# ifamp-rx.net
KiCad netlist of a schematic drawn in Altium Designer
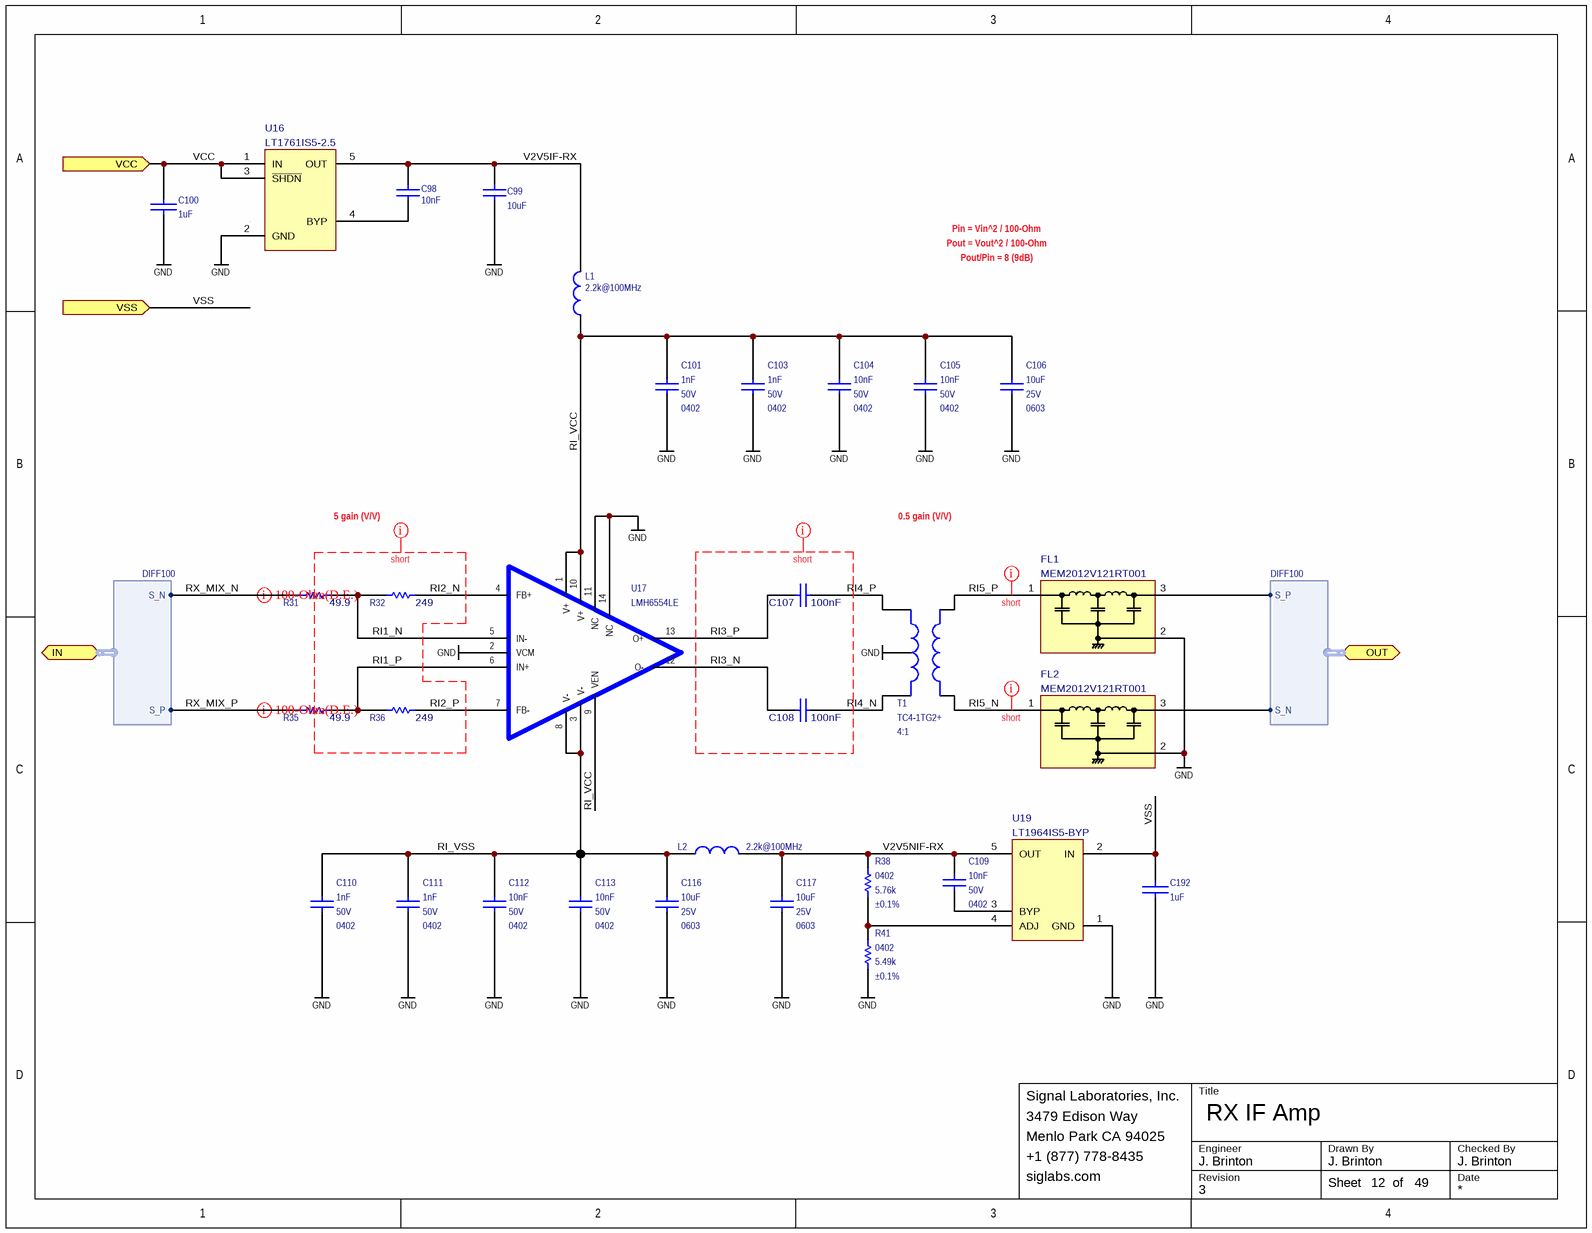
[diagram p0: ifamp-rx.SchDoc]

(export (version "E")
  (design (tool "Eeschema 10.0.6"))
  (components
    (comp (ref "C98")
      (value "10nF")
      (footprint "CAPC100X50X55L25N")
      (description "Ceramic Capacitor 10nF ±10% 50V X7R 0402")
      (fields (field (name "VOLTAGE") "50V") (field (name "MANUFACTURER") "Murata"))
      (libsource (lib "Graviton") (part "CAP 0402"))
    )
    (comp (ref "C99")
      (value "10uF")
      (footprint "CAPC160X80X90L20N")
      (description "Ceramic Capacitor 10uF ±20% 25V X5R 0603")
      (fields (field (name "MANUFACTURER") "Murata") (field (name "VOLTAGE") "25V"))
      (libsource (lib "generic") (part "CAP 0603"))
    )
    (comp (ref "C100")
      (value "1uF")
      (footprint "CAPC100X50X55L25N")
      (description "Ceramic Capacitor 1uF ±10% 10V X5R 0402")
      (fields (field (name "MANUFACTURER") "Murata") (field (name "TOLERANCE") "±10%"))
      (libsource (lib "*") (part "CAP"))
    )
    (comp (ref "C101")
      (value "1nF")
      (footprint "CAPC100X50X55L25N")
      (description "Ceramic Capacitor 1nF ±5% 50V NP0 0402")
      (fields
        (field (name "VOLTAGE") "50V")
        (field (name "MANUFACTURER") "TDK")
        (field (name "PACKAGE") "0402")
        (field (name "TOLERANCE") "±5%")
      )
      (libsource (lib "Graviton") (part "CAP 0402"))
    )
    (comp (ref "C103")
      (value "1nF")
      (footprint "CAPC100X50X55L25N")
      (description "Ceramic Capacitor 1nF ±5% 50V NP0 0402")
      (fields
        (field (name "VOLTAGE") "50V")
        (field (name "MANUFACTURER") "TDK")
        (field (name "PACKAGE") "0402")
        (field (name "TOLERANCE") "±5%")
      )
      (libsource (lib "Graviton") (part "CAP 0402"))
    )
    (comp (ref "C104")
      (value "10nF")
      (footprint "CAPC100X50X55L25N")
      (description "Ceramic Capacitor 10nF ±10% 50V X7R 0402")
      (fields
        (field (name "VOLTAGE") "50V")
        (field (name "MANUFACTURER") "Murata")
        (field (name "PACKAGE") "0402")
        (field (name "TOLERANCE") "±10%")
      )
      (libsource (lib "Graviton") (part "CAP 0402"))
    )
    (comp (ref "C105")
      (value "10nF")
      (footprint "CAPC100X50X55L25N")
      (description "Ceramic Capacitor 10nF ±10% 50V X7R 0402")
      (fields
        (field (name "VOLTAGE") "50V")
        (field (name "MANUFACTURER") "Murata")
        (field (name "PACKAGE") "0402")
        (field (name "TOLERANCE") "±10%")
      )
      (libsource (lib "Graviton") (part "CAP 0402"))
    )
    (comp (ref "C106")
      (value "10uF")
      (footprint "CAPC160X80X90L20N")
      (description "Ceramic Capacitor 10uF ±20% 25V X5R 0603")
      (fields
        (field (name "MANUFACTURER") "Murata")
        (field (name "VOLTAGE") "25V")
        (field (name "PACKAGE") "0603")
        (field (name "TOLERANCE") "±20%")
      )
      (libsource (lib "generic") (part "CAP 0603"))
    )
    (comp (ref "C107")
      (value "100nF")
      (footprint "CAPC100X50X55L25N")
      (description "Ceramic Capacitor 100nF ±10% 25V X7R 0402")
      (fields (field (name "MANUFACTURER") "Yageo") (field (name "TOLERANCE") "±10%"))
      (libsource (lib "capacitors") (part "CAP"))
    )
    (comp (ref "C108")
      (value "100nF")
      (footprint "CAPC100X50X55L25N")
      (description "Ceramic Capacitor 100nF ±10% 25V X7R 0402")
      (fields (field (name "MANUFACTURER") "Yageo") (field (name "TOLERANCE") "±10%"))
      (libsource (lib "capacitors") (part "CAP"))
    )
    (comp (ref "C109")
      (value "10nF")
      (footprint "CAPC100X50X55L25N")
      (description "Ceramic Capacitor 10nF ±10% 50V X7R 0402")
      (fields
        (field (name "VOLTAGE") "50V")
        (field (name "MANUFACTURER") "Murata")
        (field (name "PACKAGE") "0402")
        (field (name "TOLERANCE") "±10%")
      )
      (libsource (lib "Graviton") (part "CAP 0402"))
    )
    (comp (ref "C110")
      (value "1nF")
      (footprint "CAPC100X50X55L25N")
      (description "Ceramic Capacitor 1nF ±5% 50V NP0 0402")
      (fields
        (field (name "VOLTAGE") "50V")
        (field (name "MANUFACTURER") "TDK")
        (field (name "PACKAGE") "0402")
        (field (name "TOLERANCE") "±5%")
      )
      (libsource (lib "Graviton") (part "CAP 0402"))
    )
    (comp (ref "C111")
      (value "1nF")
      (footprint "CAPC100X50X55L25N")
      (description "Ceramic Capacitor 1nF ±5% 50V NP0 0402")
      (fields
        (field (name "VOLTAGE") "50V")
        (field (name "MANUFACTURER") "TDK")
        (field (name "PACKAGE") "0402")
        (field (name "TOLERANCE") "±5%")
      )
      (libsource (lib "Graviton") (part "CAP 0402"))
    )
    (comp (ref "C112")
      (value "10nF")
      (footprint "CAPC100X50X55L25N")
      (description "Ceramic Capacitor 10nF ±10% 50V X7R 0402")
      (fields
        (field (name "VOLTAGE") "50V")
        (field (name "MANUFACTURER") "Murata")
        (field (name "PACKAGE") "0402")
        (field (name "TOLERANCE") "±10%")
      )
      (libsource (lib "Graviton") (part "CAP 0402"))
    )
    (comp (ref "C113")
      (value "10nF")
      (footprint "CAPC100X50X55L25N")
      (description "Ceramic Capacitor 10nF ±10% 50V X7R 0402")
      (fields
        (field (name "VOLTAGE") "50V")
        (field (name "MANUFACTURER") "Murata")
        (field (name "PACKAGE") "0402")
        (field (name "TOLERANCE") "±10%")
      )
      (libsource (lib "Graviton") (part "CAP 0402"))
    )
    (comp (ref "C116")
      (value "10uF")
      (footprint "CAPC160X80X90L20N")
      (description "Ceramic Capacitor 10uF ±20% 25V X5R 0603")
      (fields
        (field (name "MANUFACTURER") "Murata")
        (field (name "VOLTAGE") "25V")
        (field (name "PACKAGE") "0603")
        (field (name "TOLERANCE") "±20%")
      )
      (libsource (lib "generic") (part "CAP 0603"))
    )
    (comp (ref "C117")
      (value "10uF")
      (footprint "CAPC160X80X90L20N")
      (description "Ceramic Capacitor 10uF ±20% 25V X5R 0603")
      (fields
        (field (name "MANUFACTURER") "Murata")
        (field (name "VOLTAGE") "25V")
        (field (name "PACKAGE") "0603")
        (field (name "TOLERANCE") "±20%")
      )
      (libsource (lib "generic") (part "CAP 0603"))
    )
    (comp (ref "C192")
      (value "1uF")
      (footprint "CAPC100X50X55L25N")
      (description "Ceramic Capacitor 1uF ±10% 10V X5R 0402")
      (fields (field (name "MANUFACTURER") "Murata") (field (name "TOLERANCE") "±10%"))
      (libsource (lib "*") (part "CAP"))
    )
    (comp (ref "FL1")
      (value "MEM2012V121RT001")
      (footprint "tdk:MEM2012V")
      (description "MEM2012 Series 120 MHz 10V 100mA SMT Signal Line 3-Terminal Filter")
      (fields (field (name "MANUFACTURER") "TDK"))
      (libsource (lib "tdk") (part "MEM2012V121RT001"))
    )
    (comp (ref "FL2")
      (value "MEM2012V121RT001")
      (footprint "tdk:MEM2012V")
      (description "MEM2012 Series 120 MHz 10V 100mA SMT Signal Line 3-Terminal Filter")
      (fields (field (name "MANUFACTURER") "TDK"))
      (libsource (lib "tdk") (part "MEM2012V121RT001"))
    )
    (comp (ref "L1")
      (value "2.2k@100MHz")
      (footprint "INDC1005X55N")
      (description "Ferrite Bead 2.2k@100MHz 150mA 0402")
      (fields (field (name "MANUFACTURER") "TDK") (field (name "Comment") "MMZ1005A222ET000"))
      (libsource (lib "*") (part "INDUCTANCE1"))
    )
    (comp (ref "L2")
      (value "2.2k@100MHz")
      (footprint "INDC1005X55N")
      (description "Ferrite Bead 2.2k@100MHz 150mA 0402")
      (fields (field (name "MANUFACTURER") "TDK") (field (name "Comment") "MMZ1005A222ET000"))
      (libsource (lib "*") (part "INDUCTANCE1"))
    )
    (comp (ref "R31")
      (value "49.9")
      (footprint "generic:RESC1608X55N")
      (description "Thin Film Resistor 49.9 Ohm ±0.5% 0603")
      (fields (field (name "MANUFACTURER") "Vishay") (field (name "TOLERANCE") "±0.5%"))
      (libsource (lib "Graviton") (part "RES 0603"))
    )
    (comp (ref "R32")
      (value "249")
      (footprint "generic:RESC1005X40N")
      (description "Thin Film Resistor 249 Ohm ±0.1% 0402")
      (fields (field (name "MANUFACTURER") "Vishay") (field (name "TOLERANCE") "±0.1%"))
      (libsource (lib "Graviton") (part "RES 0603"))
    )
    (comp (ref "R35")
      (value "49.9")
      (footprint "generic:RESC1608X55N")
      (description "Thin Film Resistor 49.9 Ohm ±0.5% 0603")
      (fields (field (name "MANUFACTURER") "Vishay") (field (name "TOLERANCE") "±0.5%"))
      (libsource (lib "Graviton") (part "RES 0603"))
    )
    (comp (ref "R36")
      (value "249")
      (footprint "generic:RESC1005X40N")
      (description "Thin Film Resistor 249 Ohm ±0.1% 0402")
      (fields (field (name "MANUFACTURER") "Vishay") (field (name "TOLERANCE") "±0.1%"))
      (libsource (lib "Graviton") (part "RES 0603"))
    )
    (comp (ref "R38")
      (value "5.76k")
      (footprint "RESC1005X40N")
      (description "Thin Film Resistor 5.76k +/-0.1% SMD 0402")
      (fields
        (field (name "TOLERANCE") "±0.1%")
        (field (name "MANUFACTURER") "Yageo")
        (field (name "PACKAGE") "0402")
        (field (name "Comment") "RT0402BRE075K76L")
      )
      (libsource (lib "generic") (part "RES"))
    )
    (comp (ref "R41")
      (value "5.49k")
      (footprint "RESC1005X40N")
      (description "Thin Film Resistor 5.49k +/-0.1% SMD 0402")
      (fields
        (field (name "TOLERANCE") "±0.1%")
        (field (name "MANUFACTURER") "Panasonic")
        (field (name "PACKAGE") "0402")
        (field (name "Comment") "ERA-2AEB5491X")
      )
      (libsource (lib "generic") (part "RES"))
    )
    (comp (ref "T1")
      (value "4:1")
      (footprint "AT224-1A")
      (description "RF Transformer 0.5 to 300MHz SMD")
      (fields
        (field (name "MANUFACTURER P/N") "TC4-1TG2+")
        (field (name "MANUFACTURER") "Mini-Circuits")
        (field (name "Comment") "TC4-1TG2+")
      )
      (libsource (lib "phase4") (part "TC1-1TG2+"))
    )
    (comp (ref "U16")
      (value "LT1761IS5-2.5")
      (footprint "TSOT-5")
      (description "100mA Low Noise LDO 5V")
      (fields (field (name "MANUFACTURER") "Linear Technology"))
      (libsource (lib "linear") (part "LT1761IS5-5"))
    )
    (comp (ref "U17")
      (value "LMH6554LE")
      (footprint "texas_instruments:NHJ0014A")
      (description "2.8 GHz Ultra Linear Fully Differential Amplifier")
      (fields (field (name "MANUFACTURER") "Texas Instruments"))
      (libsource (lib "ti") (part "LMH6554LE"))
    )
    (comp (ref "U19")
      (value "LT1964IS5-BYP")
      (footprint "SOT23-5")
      (description "200mA Low Noise negative-LDO")
      (fields (field (name "MANUFACTURER") "Linear Technology"))
      (libsource (lib "linear") (part "LT1964IS5-BYP"))
    )
  )
  (nets
    (net (code "2") (name "/RI1_N") (class "Default")
      (node (ref "R31") (pin "2") (pinfunction "2_2") (pintype "passive"))
      (node (ref "R32") (pin "1") (pinfunction "1_1") (pintype "passive"))
      (node (ref "U17") (pin "5") (pinfunction "IN-_5") (pintype "passive"))
    )
    (net (code "3") (name "/RI1_P") (class "Default")
      (node (ref "R35") (pin "2") (pinfunction "2_2") (pintype "passive"))
      (node (ref "R36") (pin "1") (pinfunction "1_1") (pintype "passive"))
      (node (ref "U17") (pin "6") (pinfunction "IN+_6") (pintype "passive"))
    )
    (net (code "4") (name "/RI2_N") (class "Default")
      (node (ref "R32") (pin "2") (pinfunction "2_2") (pintype "passive"))
      (node (ref "U17") (pin "4") (pinfunction "FB+_4") (pintype "passive"))
    )
    (net (code "5") (name "/RI2_P") (class "Default")
      (node (ref "R36") (pin "2") (pinfunction "2_2") (pintype "passive"))
      (node (ref "U17") (pin "7") (pinfunction "FB-_7") (pintype "passive"))
    )
    (net (code "6") (name "/RI3_N") (class "Default")
      (node (ref "C108") (pin "1") (pinfunction "1_1") (pintype "passive"))
      (node (ref "U17") (pin "12") (pinfunction "O-_12") (pintype "passive"))
    )
    (net (code "7") (name "/RI3_P") (class "Default")
      (node (ref "C107") (pin "1") (pinfunction "1_1") (pintype "passive"))
      (node (ref "U17") (pin "13") (pinfunction "O+_13") (pintype "passive"))
    )
    (net (code "8") (name "/RI4_N") (class "Default")
      (node (ref "C108") (pin "2") (pinfunction "2_2") (pintype "passive"))
      (node (ref "T1") (pin "1") (pinfunction "Sec+_1") (pintype "passive"))
    )
    (net (code "9") (name "/RI4_P") (class "Default")
      (node (ref "C107") (pin "2") (pinfunction "2_2") (pintype "passive"))
      (node (ref "T1") (pin "3") (pinfunction "Sec-_3") (pintype "passive"))
    )
    (net (code "10") (name "/RI5_N") (class "Default")
      (node (ref "FL2") (pin "1") (pinfunction "IN/OUT_1") (pintype "passive"))
      (node (ref "T1") (pin "6") (pinfunction "Pri+_6") (pintype "passive"))
    )
    (net (code "11") (name "/RI5_P") (class "Default")
      (node (ref "FL1") (pin "1") (pinfunction "IN/OUT_1") (pintype "passive"))
      (node (ref "T1") (pin "4") (pinfunction "Pri-_4") (pintype "passive"))
    )
    (net (code "12") (name "/RI_VCC") (class "Default")
      (node (ref "C101") (pin "2") (pinfunction "2_2") (pintype "passive"))
      (node (ref "C103") (pin "2") (pinfunction "2_2") (pintype "passive"))
      (node (ref "C104") (pin "2") (pinfunction "2_2") (pintype "passive"))
      (node (ref "C105") (pin "2") (pinfunction "2_2") (pintype "passive"))
      (node (ref "C106") (pin "2") (pinfunction "2_2") (pintype "passive"))
      (node (ref "L1") (pin "1") (pinfunction "1_1") (pintype "passive"))
      (node (ref "U17") (pin "1") (pinfunction "V+_1") (pintype "passive"))
      (node (ref "U17") (pin "10") (pinfunction "V+_10") (pintype "passive"))
      (node (ref "U17") (pin "9") (pinfunction "VEN_9") (pintype "passive"))
    )
    (net (code "13") (name "/RI_VSS") (class "Default")
      (node (ref "C110") (pin "2") (pinfunction "2_2") (pintype "passive"))
      (node (ref "C111") (pin "2") (pinfunction "2_2") (pintype "passive"))
      (node (ref "C112") (pin "2") (pinfunction "2_2") (pintype "passive"))
      (node (ref "C113") (pin "2") (pinfunction "2_2") (pintype "passive"))
      (node (ref "C116") (pin "2") (pinfunction "2_2") (pintype "passive"))
      (node (ref "L2") (pin "1") (pinfunction "1_1") (pintype "passive"))
      (node (ref "U17") (pin "3") (pinfunction "V-_3") (pintype "passive"))
      (node (ref "U17") (pin "8") (pinfunction "V-_8") (pintype "passive"))
    )
    (net (code "14") (name "/RX_MIX_N") (class "Default")
      (node (ref "R31") (pin "1") (pinfunction "1_1") (pintype "passive"))
    )
    (net (code "15") (name "/RX_MIX_P") (class "Default")
      (node (ref "R35") (pin "1") (pinfunction "1_1") (pintype "passive"))
    )
    (net (code "16") (name "/V2V5IF-RX") (class "Default")
      (node (ref "C98") (pin "2") (pinfunction "2_2") (pintype "passive"))
      (node (ref "C99") (pin "2") (pinfunction "2_2") (pintype "passive"))
      (node (ref "L1") (pin "2") (pinfunction "2_2") (pintype "passive"))
      (node (ref "U16") (pin "5") (pinfunction "OUT_5") (pintype "passive"))
    )
    (net (code "17") (name "/V2V5NIF-RX") (class "Default")
      (node (ref "C109") (pin "2") (pinfunction "2_2") (pintype "passive"))
      (node (ref "C117") (pin "2") (pinfunction "2_2") (pintype "passive"))
      (node (ref "L2") (pin "2") (pinfunction "2_2") (pintype "passive"))
      (node (ref "R38") (pin "2") (pinfunction "2_2") (pintype "passive"))
      (node (ref "U19") (pin "5") (pinfunction "OUT_5") (pintype "passive"))
    )
    (net (code "18") (name "/VCC") (class "Default")
      (node (ref "C100") (pin "2") (pinfunction "2_2") (pintype "passive"))
      (node (ref "U16") (pin "1") (pinfunction "IN_1") (pintype "passive"))
      (node (ref "U16") (pin "3") (pinfunction "SHDN_3") (pintype "passive"))
    )
    (net (code "19") (name "/VSS") (class "Default")
      (node (ref "C192") (pin "2") (pinfunction "2_2") (pintype "passive"))
      (node (ref "U19") (pin "2") (pinfunction "IN_2") (pintype "passive"))
    )
    (net (code "21") (name "GND") (class "Default")
      (node (ref "C100") (pin "1") (pinfunction "1_1") (pintype "passive"))
      (node (ref "C101") (pin "1") (pinfunction "1_1") (pintype "passive"))
      (node (ref "C103") (pin "1") (pinfunction "1_1") (pintype "passive"))
      (node (ref "C104") (pin "1") (pinfunction "1_1") (pintype "passive"))
      (node (ref "C105") (pin "1") (pinfunction "1_1") (pintype "passive"))
      (node (ref "C106") (pin "1") (pinfunction "1_1") (pintype "passive"))
      (node (ref "C110") (pin "1") (pinfunction "1_1") (pintype "passive"))
      (node (ref "C111") (pin "1") (pinfunction "1_1") (pintype "passive"))
      (node (ref "C112") (pin "1") (pinfunction "1_1") (pintype "passive"))
      (node (ref "C113") (pin "1") (pinfunction "1_1") (pintype "passive"))
      (node (ref "C116") (pin "1") (pinfunction "1_1") (pintype "passive"))
      (node (ref "C117") (pin "1") (pinfunction "1_1") (pintype "passive"))
      (node (ref "C192") (pin "1") (pinfunction "1_1") (pintype "passive"))
      (node (ref "C99") (pin "1") (pinfunction "1_1") (pintype "passive"))
      (node (ref "FL1") (pin "2") (pinfunction "GND_2") (pintype "power_in"))
      (node (ref "FL2") (pin "2") (pinfunction "GND_2") (pintype "power_in"))
      (node (ref "R41") (pin "1") (pinfunction "1_1") (pintype "passive"))
      (node (ref "T1") (pin "2") (pinfunction "SecCT_2") (pintype "passive"))
      (node (ref "U16") (pin "2") (pinfunction "GND_2") (pintype "passive"))
      (node (ref "U17") (pin "11") (pinfunction "NC_11") (pintype "passive"))
      (node (ref "U17") (pin "14") (pinfunction "NC_14") (pintype "passive"))
      (node (ref "U17") (pin "2") (pinfunction "VCM_2") (pintype "passive"))
      (node (ref "U19") (pin "1") (pinfunction "GND_1") (pintype "passive"))
    )
    (net (code "22") (name "Net-(U16-BYP)") (class "Default")
      (node (ref "C98") (pin "1") (pinfunction "1_1") (pintype "passive"))
      (node (ref "U16") (pin "4") (pinfunction "BYP_4") (pintype "passive"))
    )
    (net (code "23") (name "Net-(U19-ADJ)") (class "Default")
      (node (ref "R38") (pin "1") (pinfunction "1_1") (pintype "passive"))
      (node (ref "R41") (pin "2") (pinfunction "2_2") (pintype "passive"))
      (node (ref "U19") (pin "4") (pinfunction "ADJ_4") (pintype "passive"))
    )
    (net (code "24") (name "Net-(U19-BYP)") (class "Default")
      (node (ref "C109") (pin "1") (pinfunction "1_1") (pintype "passive"))
      (node (ref "U19") (pin "3") (pinfunction "BYP_3") (pintype "passive"))
    )
    (net (code "25") (name "unconnected-(FL1-OUT{slash}IN-Pad3)") (class "Default")
      (node (ref "FL1") (pin "3") (pinfunction "OUT/IN_3") (pintype "passive"))
    )
    (net (code "26") (name "unconnected-(FL2-OUT{slash}IN-Pad3)") (class "Default")
      (node (ref "FL2") (pin "3") (pinfunction "OUT/IN_3") (pintype "passive"))
    )
  )
)
